# SCH_PIEZO_CRYSTAL_DAC_2022-01-11.net
KiCad netlist of a schematic drawn in EasyEDA
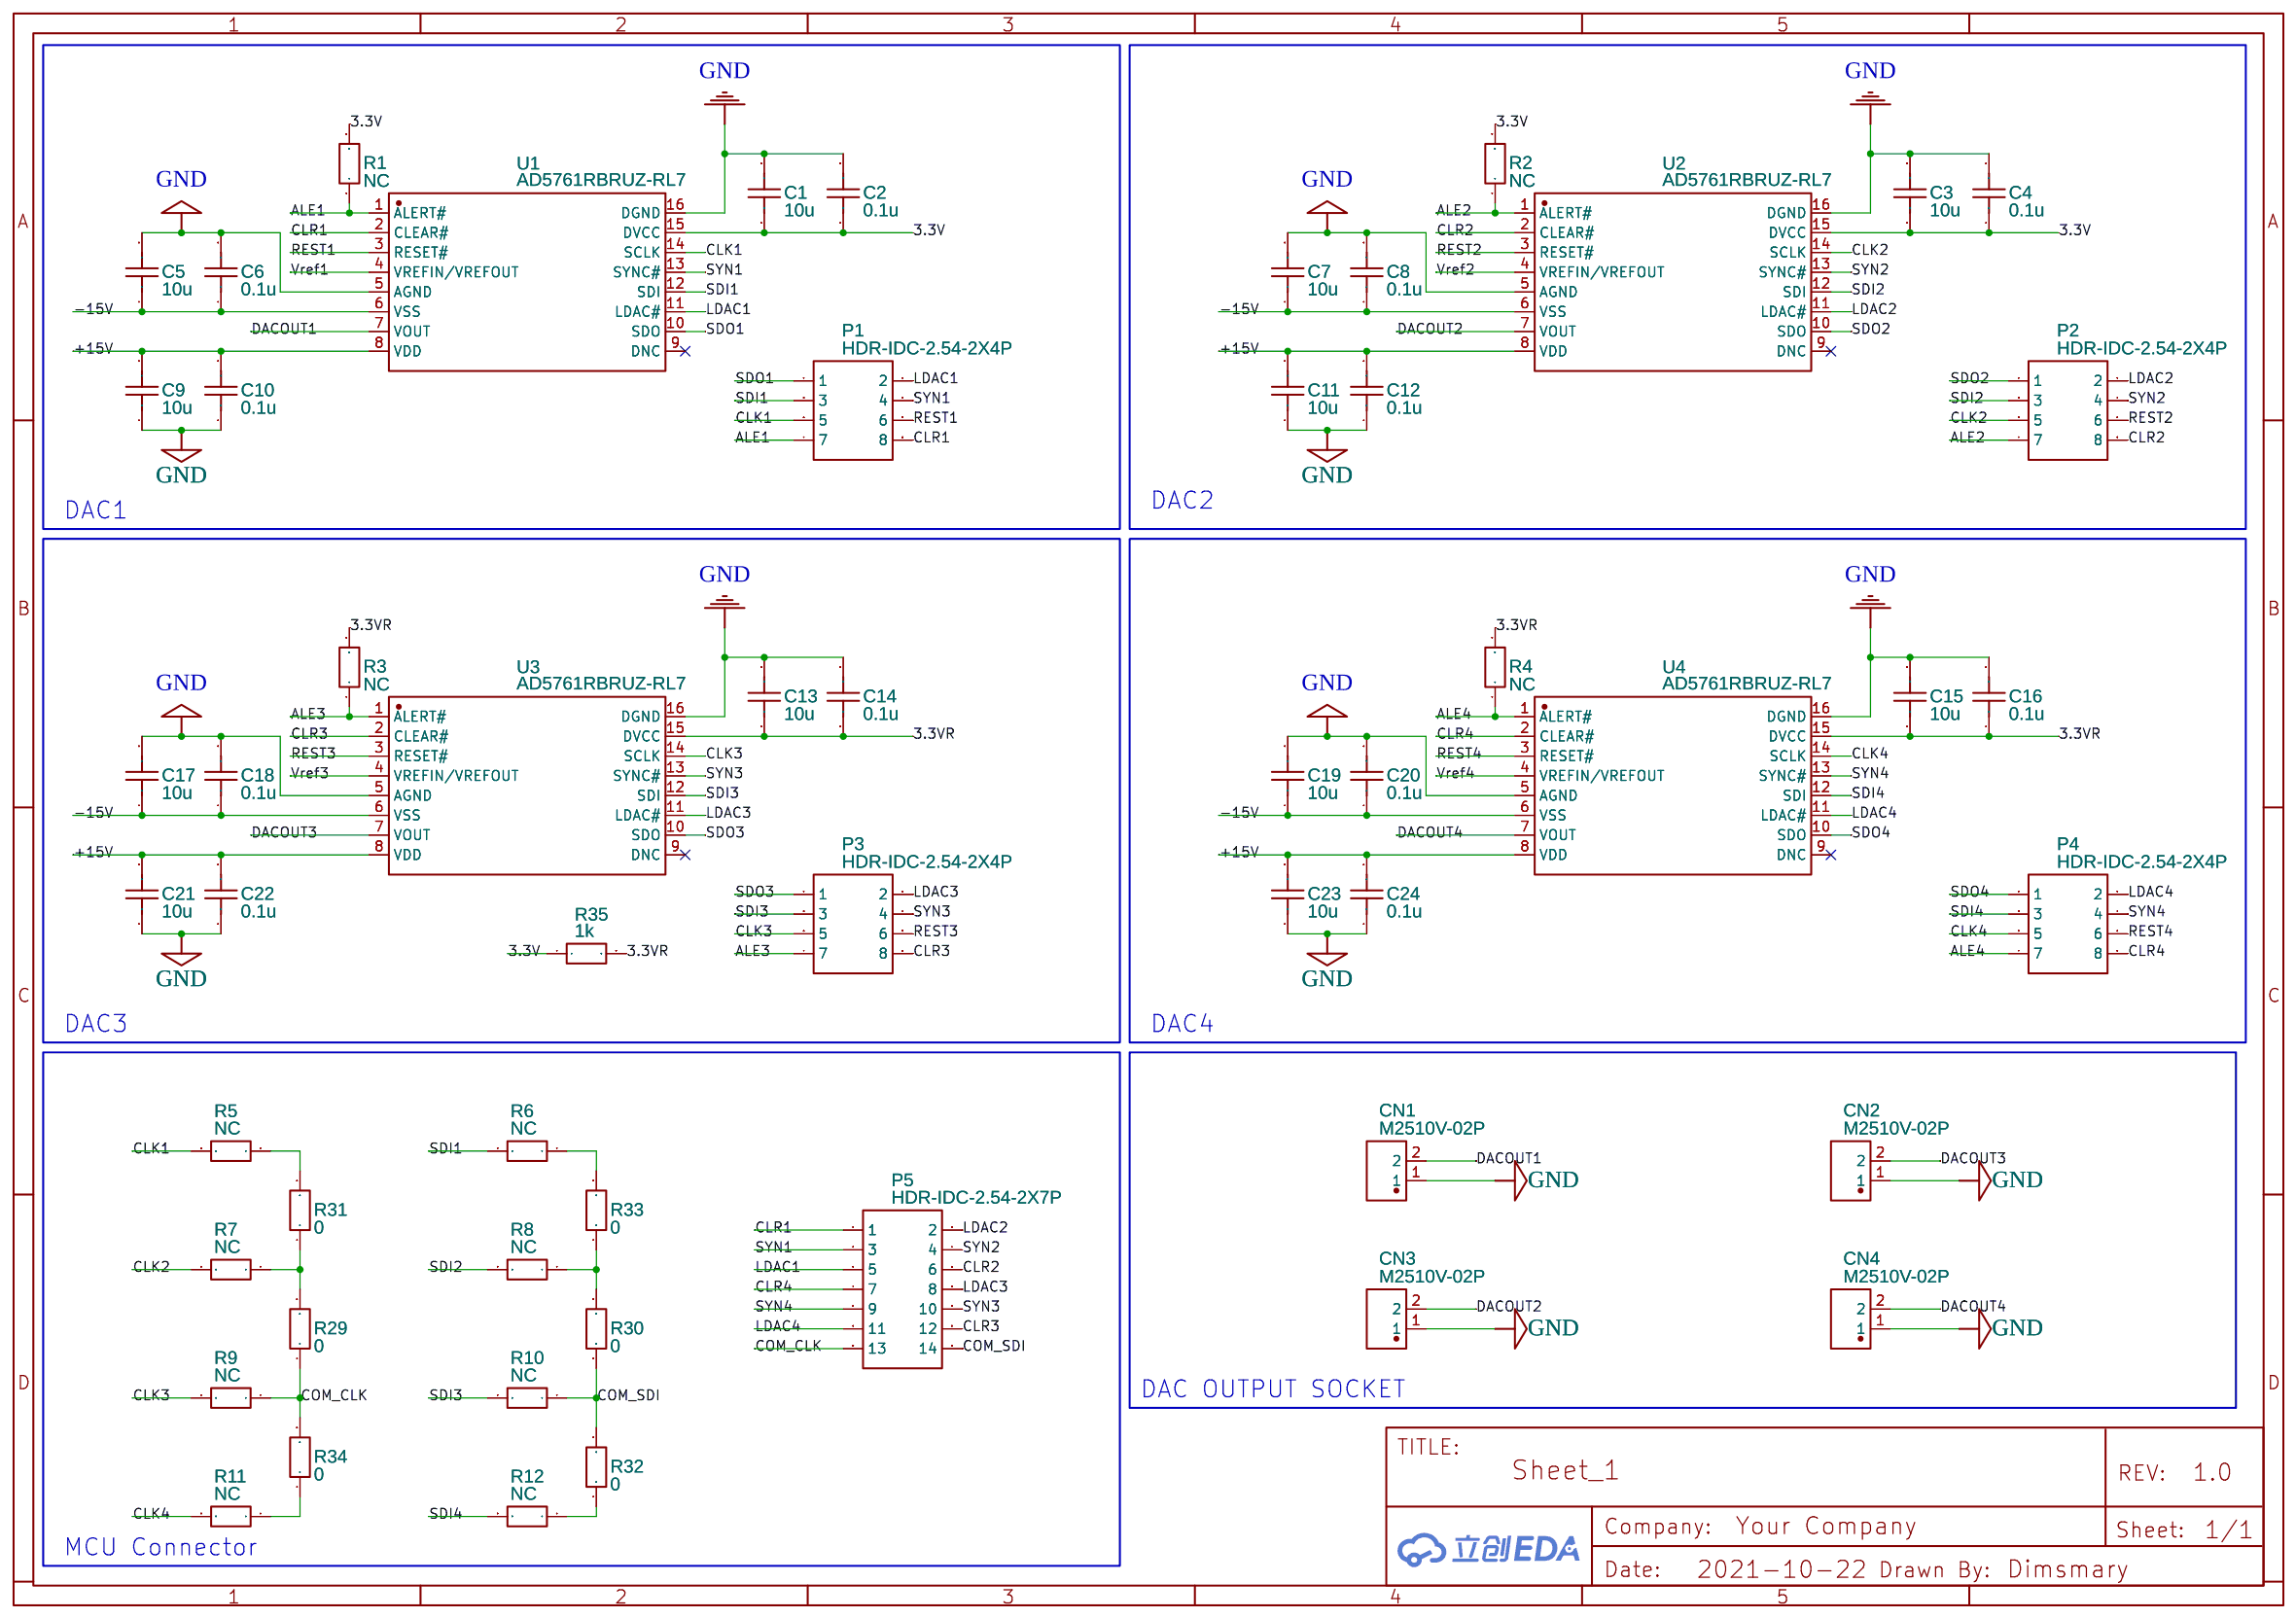
[diagram p0: DACs]
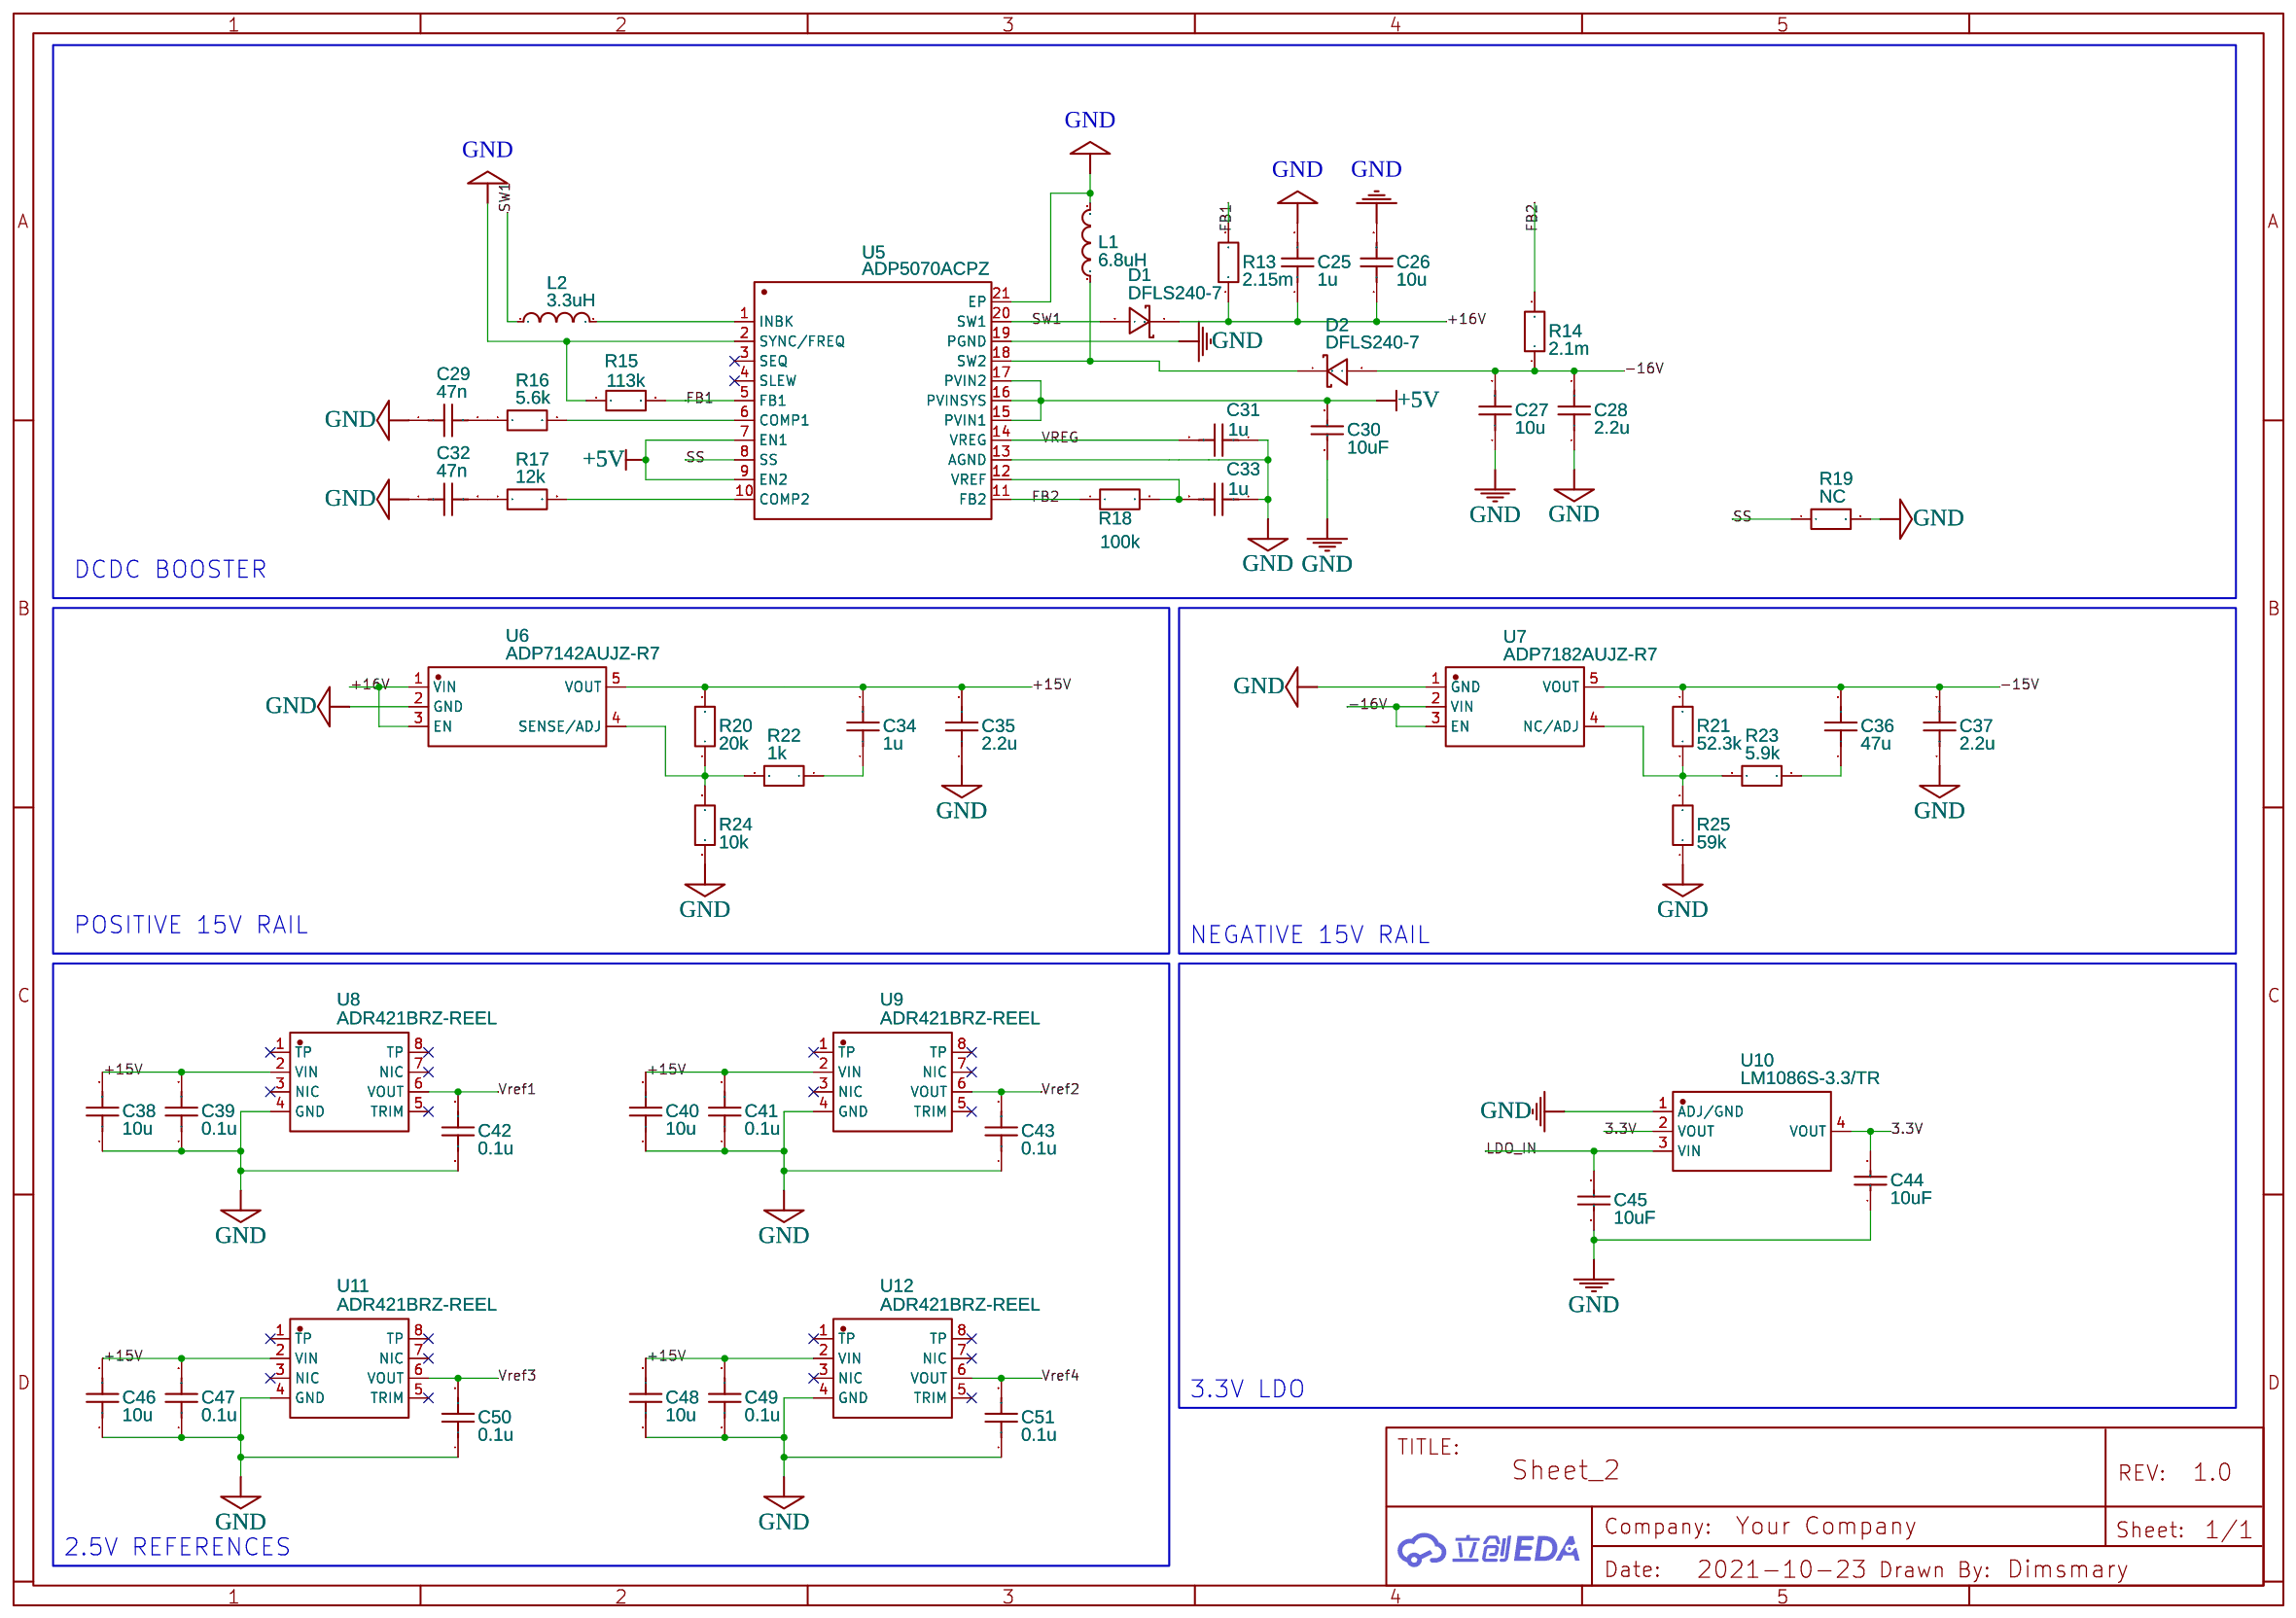
[diagram p1: PowerRail]
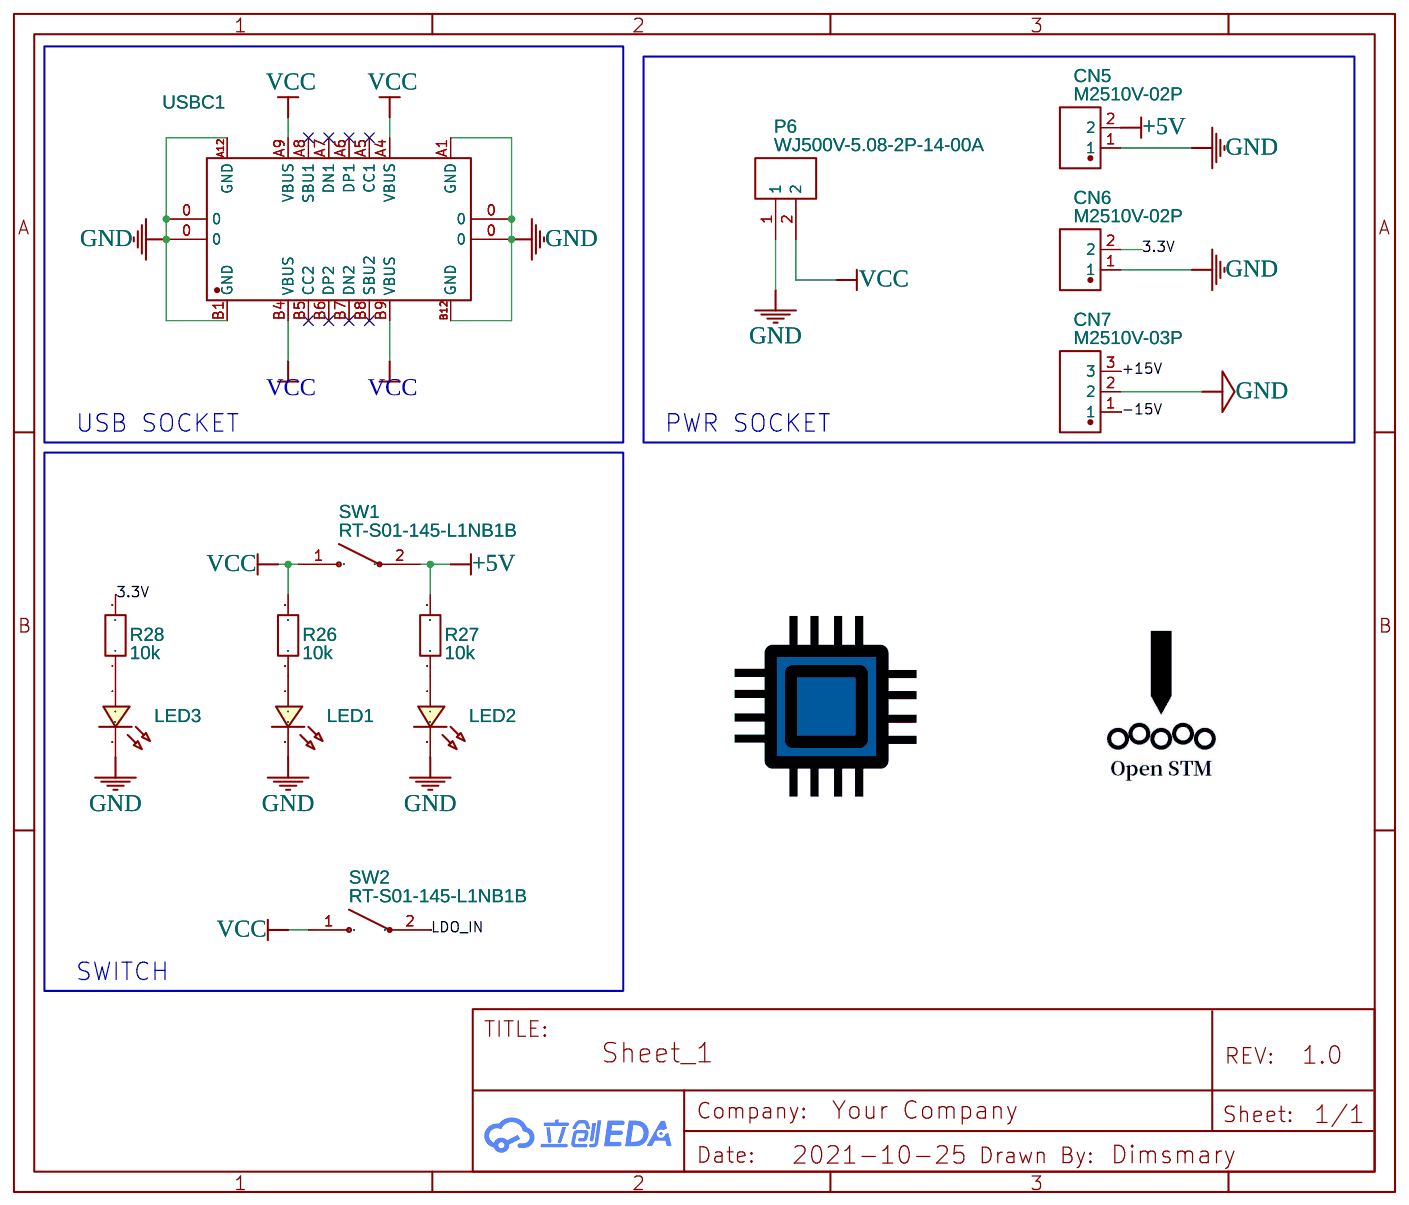
[diagram p2: PowerInput]

(export (version "E")
  (design (tool "Eeschema 10.0.6"))
  (components
    (comp (ref "C1") (value "10u") (libsource (lib "") (part "C_0603_US")))
    (comp (ref "C2") (value "0.1u") (libsource (lib "") (part "C_0603_US")))
    (comp (ref "C3") (value "10u") (libsource (lib "") (part "C_0603_US")))
    (comp (ref "C4") (value "0.1u") (libsource (lib "") (part "C_0603_US")))
    (comp (ref "C5") (value "10u") (libsource (lib "") (part "C_0603_US")))
    (comp (ref "C6") (value "0.1u") (libsource (lib "") (part "C_0603_US")))
    (comp (ref "C7") (value "10u") (libsource (lib "") (part "C_0603_US")))
    (comp (ref "C8") (value "0.1u") (libsource (lib "") (part "C_0603_US")))
    (comp (ref "C9") (value "10u") (libsource (lib "") (part "C_0603_US")))
    (comp (ref "C10") (value "0.1u") (libsource (lib "") (part "C_0603_US")))
    (comp (ref "C11") (value "10u") (libsource (lib "") (part "C_0603_US")))
    (comp (ref "C12") (value "0.1u") (libsource (lib "") (part "C_0603_US")))
    (comp (ref "C13") (value "10u") (libsource (lib "") (part "C_0603_US")))
    (comp (ref "C14") (value "0.1u") (libsource (lib "") (part "C_0603_US")))
    (comp (ref "C15") (value "10u") (libsource (lib "") (part "C_0603_US")))
    (comp (ref "C16") (value "0.1u") (libsource (lib "") (part "C_0603_US")))
    (comp (ref "C17") (value "10u") (libsource (lib "") (part "C_0603_US")))
    (comp (ref "C18") (value "0.1u") (libsource (lib "") (part "C_0603_US")))
    (comp (ref "C19") (value "10u") (libsource (lib "") (part "C_0603_US")))
    (comp (ref "C20") (value "0.1u") (libsource (lib "") (part "C_0603_US")))
    (comp (ref "C21") (value "10u") (libsource (lib "") (part "C_0603_US")))
    (comp (ref "C22") (value "0.1u") (libsource (lib "") (part "C_0603_US")))
    (comp (ref "C23") (value "10u") (libsource (lib "") (part "C_0603_US")))
    (comp (ref "C24") (value "0.1u") (libsource (lib "") (part "C_0603_US")))
    (comp (ref "CN1")
      (value "M2510V-02P")
      (fields (field (name "BOM_Supplier Part") "C2764790"))
      (libsource (lib "") (part "M2510V-02P"))
    )
    (comp (ref "CN2")
      (value "M2510V-02P")
      (fields (field (name "BOM_Supplier Part") "C2764790"))
      (libsource (lib "") (part "M2510V-02P"))
    )
    (comp (ref "CN3")
      (value "M2510V-02P")
      (fields (field (name "BOM_Supplier Part") "C2764790"))
      (libsource (lib "") (part "M2510V-02P"))
    )
    (comp (ref "CN4")
      (value "M2510V-02P")
      (fields (field (name "BOM_Supplier Part") "C2764790"))
      (libsource (lib "") (part "M2510V-02P"))
    )
    (comp (ref "P1")
      (value "HDR-IDC-2.54-2X4P")
      (fields
        (field (name "BOM_Manufacturer Part") "IDC Box 2X4 2.54MM")
        (field (name "BOM_Supplier Part") "C9135")
      )
      (libsource (lib "") (part "HDR-IDC-2.54-2X4P"))
    )
    (comp (ref "P2")
      (value "HDR-IDC-2.54-2X4P")
      (fields
        (field (name "BOM_Manufacturer Part") "IDC Box 2X4 2.54MM")
        (field (name "BOM_Supplier Part") "C9135")
      )
      (libsource (lib "") (part "HDR-IDC-2.54-2X4P"))
    )
    (comp (ref "P3")
      (value "HDR-IDC-2.54-2X4P")
      (fields
        (field (name "BOM_Manufacturer Part") "IDC Box 2X4 2.54MM")
        (field (name "BOM_Supplier Part") "C9135")
      )
      (libsource (lib "") (part "HDR-IDC-2.54-2X4P"))
    )
    (comp (ref "P4")
      (value "HDR-IDC-2.54-2X4P")
      (fields
        (field (name "BOM_Manufacturer Part") "IDC Box 2X4 2.54MM")
        (field (name "BOM_Supplier Part") "C9135")
      )
      (libsource (lib "") (part "HDR-IDC-2.54-2X4P"))
    )
    (comp (ref "P5")
      (value "HDR-IDC-2.54-2X7P")
      (fields
        (field (name "BOM_Manufacturer Part") "2X7 2.54mm IDC Box")
        (field (name "BOM_Supplier Part") "C11215")
      )
      (libsource (lib "") (part "HDR-IDC-2.54-2X7P"))
    )
    (comp (ref "R1") (value "NC") (libsource (lib "") (part "R_0603_EU_1")))
    (comp (ref "R2") (value "NC") (libsource (lib "") (part "R_0603_EU_1")))
    (comp (ref "R3") (value "NC") (libsource (lib "") (part "R_0603_EU_1")))
    (comp (ref "R4") (value "NC") (libsource (lib "") (part "R_0603_EU_1")))
    (comp (ref "R5") (value "NC") (libsource (lib "") (part "R_0603_EU")))
    (comp (ref "R6") (value "NC") (libsource (lib "") (part "R_0603_EU")))
    (comp (ref "R7") (value "NC") (libsource (lib "") (part "R_0603_EU")))
    (comp (ref "R8") (value "NC") (libsource (lib "") (part "R_0603_EU")))
    (comp (ref "R9") (value "NC") (libsource (lib "") (part "R_0603_EU")))
    (comp (ref "R10") (value "NC") (libsource (lib "") (part "R_0603_EU")))
    (comp (ref "R11") (value "NC") (libsource (lib "") (part "R_0603_EU")))
    (comp (ref "R12") (value "NC") (libsource (lib "") (part "R_0603_EU")))
    (comp (ref "R29") (value "0") (libsource (lib "") (part "R_1206_EU")))
    (comp (ref "R30") (value "0") (libsource (lib "") (part "R_1206_EU")))
    (comp (ref "R31") (value "0") (libsource (lib "") (part "R_1206_EU")))
    (comp (ref "R32") (value "0") (libsource (lib "") (part "R_1206_EU")))
    (comp (ref "R33") (value "0") (libsource (lib "") (part "R_1206_EU")))
    (comp (ref "R34") (value "0") (libsource (lib "") (part "R_1206_EU")))
    (comp (ref "R35") (value "1k") (libsource (lib "") (part "R_2512_EU")))
    (comp (ref "U1")
      (value "AD5761RBRUZ-RL7")
      (fields (field (name "BOM_Supplier Part") "C515877"))
      (libsource (lib "") (part "AD5761RBRUZ-RL7"))
    )
    (comp (ref "U2")
      (value "AD5761RBRUZ-RL7")
      (fields (field (name "BOM_Supplier Part") "C515877"))
      (libsource (lib "") (part "AD5761RBRUZ-RL7"))
    )
    (comp (ref "U3")
      (value "AD5761RBRUZ-RL7")
      (fields (field (name "BOM_Supplier Part") "C515877"))
      (libsource (lib "") (part "AD5761RBRUZ-RL7"))
    )
    (comp (ref "U4")
      (value "AD5761RBRUZ-RL7")
      (fields (field (name "BOM_Supplier Part") "C515877"))
      (libsource (lib "") (part "AD5761RBRUZ-RL7"))
    )
    (comp (ref "C25") (value "1u") (libsource (lib "") (part "C_0603_US")))
    (comp (ref "C26") (value "10u") (libsource (lib "") (part "C_0603_US")))
    (comp (ref "C27") (value "10u") (libsource (lib "") (part "C_0603_US")))
    (comp (ref "C28") (value "2.2u") (libsource (lib "") (part "C_0603_US")))
    (comp (ref "C29") (value "47n") (libsource (lib "") (part "C_0603_US_2")))
    (comp (ref "C30")
      (value "10uF")
      (fields
        (field (name "BOM_Manufacturer Part") "CL21A106KOQNNNE")
        (field (name "BOM_Supplier Part") "C1713")
      )
      (libsource (lib "") (part "CL21A106KOQNNNE"))
    )
    (comp (ref "C31") (value "1u") (libsource (lib "") (part "C_0603_US_1")))
    (comp (ref "C32") (value "47n") (libsource (lib "") (part "C_0603_US_2")))
    (comp (ref "C33") (value "1u") (libsource (lib "") (part "C_0603_US_1")))
    (comp (ref "C34") (value "1u") (libsource (lib "") (part "C_0603_US")))
    (comp (ref "C35") (value "2.2u") (libsource (lib "") (part "C_0603_US")))
    (comp (ref "C36") (value "47u") (libsource (lib "") (part "C_0603_US")))
    (comp (ref "C37") (value "2.2u") (libsource (lib "") (part "C_0603_US")))
    (comp (ref "C38") (value "10u") (libsource (lib "") (part "C_0603_US")))
    (comp (ref "C39") (value "0.1u") (libsource (lib "") (part "C_0603_US")))
    (comp (ref "C40") (value "10u") (libsource (lib "") (part "C_0603_US")))
    (comp (ref "C41") (value "0.1u") (libsource (lib "") (part "C_0603_US")))
    (comp (ref "C42") (value "0.1u") (libsource (lib "") (part "C_0603_US")))
    (comp (ref "C43") (value "0.1u") (libsource (lib "") (part "C_0603_US")))
    (comp (ref "C44")
      (value "10uF")
      (fields
        (field (name "BOM_Manufacturer Part") "CL21A106KOQNNNE")
        (field (name "BOM_Supplier Part") "C1713")
      )
      (libsource (lib "") (part "CL21A106KOQNNNE"))
    )
    (comp (ref "C45")
      (value "10uF")
      (fields
        (field (name "BOM_Manufacturer Part") "CL21A106KOQNNNE")
        (field (name "BOM_Supplier Part") "C1713")
      )
      (libsource (lib "") (part "CL21A106KOQNNNE"))
    )
    (comp (ref "C46") (value "10u") (libsource (lib "") (part "C_0603_US")))
    (comp (ref "C47") (value "0.1u") (libsource (lib "") (part "C_0603_US")))
    (comp (ref "C48") (value "10u") (libsource (lib "") (part "C_0603_US")))
    (comp (ref "C49") (value "0.1u") (libsource (lib "") (part "C_0603_US")))
    (comp (ref "C50") (value "0.1u") (libsource (lib "") (part "C_0603_US")))
    (comp (ref "C51") (value "0.1u") (libsource (lib "") (part "C_0603_US")))
    (comp (ref "D1")
      (value "DFLS240-7")
      (fields (field (name "BOM_Supplier Part") "C124195"))
      (libsource (lib "") (part "DFLS240-7"))
    )
    (comp (ref "D2")
      (value "DFLS240-7")
      (fields (field (name "BOM_Supplier Part") "C124195"))
      (libsource (lib "") (part "DFLS240-7_1"))
    )
    (comp (ref "L1")
      (value "6.8uH")
      (fields
        (field (name "BOM_Manufacturer Part") "LBM2016T6R8J")
        (field (name "BOM_Supplier Part") "C222609")
      )
      (libsource (lib "") (part "LBM2016T6R8J"))
    )
    (comp (ref "L2")
      (value "3.3uH")
      (fields
        (field (name "BOM_Manufacturer Part") "LBM2016T3R3J")
        (field (name "BOM_Supplier Part") "C222605")
      )
      (libsource (lib "") (part "LBM2016T3R3J"))
    )
    (comp (ref "R13") (value "2.15m") (libsource (lib "") (part "R_0603_EU")))
    (comp (ref "R14") (value "2.1m") (libsource (lib "") (part "R_0603_EU")))
    (comp (ref "R15") (value "113k") (libsource (lib "") (part "R_0603_EU_2")))
    (comp (ref "R16") (value "5.6k") (libsource (lib "") (part "R_0603_EU_2")))
    (comp (ref "R17") (value "12k") (libsource (lib "") (part "R_0603_EU_2")))
    (comp (ref "R18") (value "100k") (libsource (lib "") (part "R_0603_EU_2")))
    (comp (ref "R19") (value "NC") (libsource (lib "") (part "R_0603_EU_2")))
    (comp (ref "R20") (value "20k") (libsource (lib "") (part "R_0603_EU")))
    (comp (ref "R21") (value "52.3k") (libsource (lib "") (part "R_0603_EU")))
    (comp (ref "R22") (value "1k") (libsource (lib "") (part "R_0603_EU_1")))
    (comp (ref "R23") (value "5.9k") (libsource (lib "") (part "R_0603_EU_1")))
    (comp (ref "R24") (value "10k") (libsource (lib "") (part "R_0603_EU")))
    (comp (ref "R25") (value "59k") (libsource (lib "") (part "R_0603_EU")))
    (comp (ref "U5")
      (value "ADP5070ACPZ")
      (fields (field (name "BOM_Supplier Part") "C659267"))
      (libsource (lib "") (part "ADP5070ACPZ"))
    )
    (comp (ref "U6")
      (value "ADP7142AUJZ-R7")
      (fields (field (name "BOM_Supplier Part") "C514356"))
      (libsource (lib "") (part "ADP7142AUJZ-R7"))
    )
    (comp (ref "U7")
      (value "ADP7182AUJZ-R7")
      (fields (field (name "BOM_Supplier Part") "C514358"))
      (libsource (lib "") (part "ADP7182AUJZ-R7"))
    )
    (comp (ref "U8")
      (value "ADR421BRZ-REEL")
      (fields (field (name "BOM_Supplier Part") "C496503"))
      (libsource (lib "") (part "ADR421BRZ-REEL"))
    )
    (comp (ref "U9")
      (value "ADR421BRZ-REEL")
      (fields (field (name "BOM_Supplier Part") "C496503"))
      (libsource (lib "") (part "ADR421BRZ-REEL"))
    )
    (comp (ref "U10")
      (value "LM1086S-3.3/TR")
      (fields (field (name "BOM_Supplier Part") "C444378"))
      (libsource (lib "") (part "LM1086S-3.3/TR"))
    )
    (comp (ref "U11")
      (value "ADR421BRZ-REEL")
      (fields (field (name "BOM_Supplier Part") "C496503"))
      (libsource (lib "") (part "ADR421BRZ-REEL"))
    )
    (comp (ref "U12")
      (value "ADR421BRZ-REEL")
      (fields (field (name "BOM_Supplier Part") "C496503"))
      (libsource (lib "") (part "ADR421BRZ-REEL"))
    )
    (comp (ref "CN5")
      (value "M2510V-02P")
      (fields (field (name "BOM_Supplier Part") "C2764790"))
      (libsource (lib "") (part "M2510V-02P"))
    )
    (comp (ref "CN6")
      (value "M2510V-02P")
      (fields (field (name "BOM_Supplier Part") "C2764790"))
      (libsource (lib "") (part "M2510V-02P"))
    )
    (comp (ref "CN7")
      (value "M2510V-03P")
      (fields (field (name "BOM_Supplier Part") "C2764791"))
      (libsource (lib "") (part "M2510V-03P"))
    )
    (comp (ref "LED1")
      (value "LED-0603_R")
      (fields
        (field (name "BOM_Manufacturer Part") "19-217/R6C-AL1M2VY/3T")
        (field (name "BOM_Supplier Part") "C72044")
      )
      (libsource (lib "") (part "LED-0603_R"))
    )
    (comp (ref "LED2")
      (value "LED-0603_R")
      (fields
        (field (name "BOM_Manufacturer Part") "19-217/R6C-AL1M2VY/3T")
        (field (name "BOM_Supplier Part") "C72044")
      )
      (libsource (lib "") (part "LED-0603_R"))
    )
    (comp (ref "LED3")
      (value "LED-0603_R")
      (fields
        (field (name "BOM_Manufacturer Part") "19-217/R6C-AL1M2VY/3T")
        (field (name "BOM_Supplier Part") "C72044")
      )
      (libsource (lib "") (part "LED-0603_R"))
    )
    (comp (ref "P6")
      (value "WJ500V-5.08-2P-14-00A")
      (fields (field (name "BOM_Supplier Part") "C8465"))
      (libsource (lib "") (part "WJ500V-5.08-2P-14-00A"))
    )
    (comp (ref "R26") (value "10k") (libsource (lib "") (part "R_0603_EU")))
    (comp (ref "R27") (value "10k") (libsource (lib "") (part "R_0603_EU")))
    (comp (ref "R28") (value "10k") (libsource (lib "") (part "R_0603_EU")))
    (comp (ref "SW1")
      (value "RT-S01-145-L1NB1B")
      (fields (field (name "BOM_Supplier Part") "C312627"))
      (libsource (lib "") (part "RT-S01-145-L1NB1B"))
    )
    (comp (ref "SW2")
      (value "RT-S01-145-L1NB1B")
      (fields (field (name "BOM_Supplier Part") "C312627"))
      (libsource (lib "") (part "RT-S01-145-L1NB1B"))
    )
    (comp (ref "USBC1")
      (value "TYPE-C-31-M-12")
      (fields (field (name "BOM_Supplier Part") "C165948"))
      (libsource (lib "") (part "Unknown_165_-705"))
    )
  )
  (nets
    (net (code "1") (name "+5V") (class "Default")
      (node (ref "C30") (pin "2") (pinfunction "2_2") (pintype "input"))
      (node (ref "CN5") (pin "2") (pinfunction "2_2") (pintype "unspecified"))
      (node (ref "R27") (pin "2") (pinfunction "2_2") (pintype "unspecified"))
      (node (ref "SW1") (pin "2") (pinfunction "2_2") (pintype "unspecified"))
      (node (ref "U5") (pin "15") (pinfunction "PVIN1_15") (pintype "unspecified"))
      (node (ref "U5") (pin "16") (pinfunction "PVINSYS_16") (pintype "unspecified"))
      (node (ref "U5") (pin "17") (pinfunction "PVIN2_17") (pintype "unspecified"))
      (node (ref "U5") (pin "7") (pinfunction "EN1_7") (pintype "unspecified"))
      (node (ref "U5") (pin "9") (pinfunction "EN2_9") (pintype "unspecified"))
    )
    (net (code "2") (name "+15V") (class "Default")
      (node (ref "C10") (pin "2") (pinfunction "2_2") (pintype "unspecified"))
      (node (ref "C11") (pin "2") (pinfunction "2_2") (pintype "unspecified"))
      (node (ref "C12") (pin "2") (pinfunction "2_2") (pintype "unspecified"))
      (node (ref "C21") (pin "2") (pinfunction "2_2") (pintype "unspecified"))
      (node (ref "C22") (pin "2") (pinfunction "2_2") (pintype "unspecified"))
      (node (ref "C23") (pin "2") (pinfunction "2_2") (pintype "unspecified"))
      (node (ref "C24") (pin "2") (pinfunction "2_2") (pintype "unspecified"))
      (node (ref "C34") (pin "2") (pinfunction "2_2") (pintype "unspecified"))
      (node (ref "C35") (pin "2") (pinfunction "2_2") (pintype "unspecified"))
      (node (ref "C38") (pin "2") (pinfunction "2_2") (pintype "unspecified"))
      (node (ref "C39") (pin "2") (pinfunction "2_2") (pintype "unspecified"))
      (node (ref "C40") (pin "2") (pinfunction "2_2") (pintype "unspecified"))
      (node (ref "C41") (pin "2") (pinfunction "2_2") (pintype "unspecified"))
      (node (ref "C46") (pin "2") (pinfunction "2_2") (pintype "unspecified"))
      (node (ref "C47") (pin "2") (pinfunction "2_2") (pintype "unspecified"))
      (node (ref "C48") (pin "2") (pinfunction "2_2") (pintype "unspecified"))
      (node (ref "C49") (pin "2") (pinfunction "2_2") (pintype "unspecified"))
      (node (ref "C9") (pin "2") (pinfunction "2_2") (pintype "unspecified"))
      (node (ref "CN7") (pin "3") (pinfunction "3_3") (pintype "unspecified"))
      (node (ref "R20") (pin "2") (pinfunction "2_2") (pintype "unspecified"))
      (node (ref "U1") (pin "8") (pinfunction "VDD_8") (pintype "unspecified"))
      (node (ref "U11") (pin "2") (pinfunction "VIN_2") (pintype "unspecified"))
      (node (ref "U12") (pin "2") (pinfunction "VIN_2") (pintype "unspecified"))
      (node (ref "U2") (pin "8") (pinfunction "VDD_8") (pintype "unspecified"))
      (node (ref "U3") (pin "8") (pinfunction "VDD_8") (pintype "unspecified"))
      (node (ref "U4") (pin "8") (pinfunction "VDD_8") (pintype "unspecified"))
      (node (ref "U6") (pin "5") (pinfunction "VOUT_5") (pintype "unspecified"))
      (node (ref "U8") (pin "2") (pinfunction "VIN_2") (pintype "unspecified"))
      (node (ref "U9") (pin "2") (pinfunction "VIN_2") (pintype "unspecified"))
    )
    (net (code "3") (name "+16V") (class "Default")
      (node (ref "C25") (pin "1") (pinfunction "1_1") (pintype "unspecified"))
      (node (ref "C26") (pin "1") (pinfunction "1_1") (pintype "unspecified"))
      (node (ref "D1") (pin "1") (pinfunction "C_1") (pintype "unspecified"))
      (node (ref "R13") (pin "1") (pinfunction "1_1") (pintype "unspecified"))
      (node (ref "U6") (pin "1") (pinfunction "VIN_1") (pintype "unspecified"))
      (node (ref "U6") (pin "3") (pinfunction "EN_3") (pintype "unspecified"))
    )
    (net (code "4") (name "-15V") (class "Default")
      (node (ref "C17") (pin "1") (pinfunction "1_1") (pintype "unspecified"))
      (node (ref "C18") (pin "1") (pinfunction "1_1") (pintype "unspecified"))
      (node (ref "C19") (pin "1") (pinfunction "1_1") (pintype "unspecified"))
      (node (ref "C20") (pin "1") (pinfunction "1_1") (pintype "unspecified"))
      (node (ref "C36") (pin "2") (pinfunction "2_2") (pintype "unspecified"))
      (node (ref "C37") (pin "2") (pinfunction "2_2") (pintype "unspecified"))
      (node (ref "C5") (pin "1") (pinfunction "1_1") (pintype "unspecified"))
      (node (ref "C6") (pin "1") (pinfunction "1_1") (pintype "unspecified"))
      (node (ref "C7") (pin "1") (pinfunction "1_1") (pintype "unspecified"))
      (node (ref "C8") (pin "1") (pinfunction "1_1") (pintype "unspecified"))
      (node (ref "CN7") (pin "1") (pinfunction "1_1") (pintype "unspecified"))
      (node (ref "R21") (pin "2") (pinfunction "2_2") (pintype "unspecified"))
      (node (ref "U1") (pin "6") (pinfunction "VSS_6") (pintype "unspecified"))
      (node (ref "U2") (pin "6") (pinfunction "VSS_6") (pintype "unspecified"))
      (node (ref "U3") (pin "6") (pinfunction "VSS_6") (pintype "unspecified"))
      (node (ref "U4") (pin "6") (pinfunction "VSS_6") (pintype "unspecified"))
      (node (ref "U7") (pin "5") (pinfunction "VOUT_5") (pintype "unspecified"))
    )
    (net (code "5") (name "-16V") (class "Default")
      (node (ref "C27") (pin "2") (pinfunction "2_2") (pintype "unspecified"))
      (node (ref "C28") (pin "2") (pinfunction "2_2") (pintype "unspecified"))
      (node (ref "D2") (pin "2") (pinfunction "A_2") (pintype "unspecified"))
      (node (ref "R14") (pin "1") (pinfunction "1_1") (pintype "unspecified"))
      (node (ref "U7") (pin "2") (pinfunction "VIN_2") (pintype "unspecified"))
      (node (ref "U7") (pin "3") (pinfunction "EN_3") (pintype "unspecified"))
    )
    (net (code "6") (name "3.3V") (class "Default")
      (node (ref "C1") (pin "1") (pinfunction "1_1") (pintype "unspecified"))
      (node (ref "C2") (pin "1") (pinfunction "1_1") (pintype "unspecified"))
      (node (ref "C3") (pin "1") (pinfunction "1_1") (pintype "unspecified"))
      (node (ref "C4") (pin "1") (pinfunction "1_1") (pintype "unspecified"))
      (node (ref "C44") (pin "2") (pinfunction "2_2") (pintype "input"))
      (node (ref "CN6") (pin "2") (pinfunction "2_2") (pintype "unspecified"))
      (node (ref "R1") (pin "2") (pinfunction "2_2") (pintype "unspecified"))
      (node (ref "R2") (pin "2") (pinfunction "2_2") (pintype "unspecified"))
      (node (ref "R28") (pin "2") (pinfunction "2_2") (pintype "unspecified"))
      (node (ref "R35") (pin "1") (pinfunction "1_1") (pintype "unspecified"))
      (node (ref "U1") (pin "15") (pinfunction "DVCC_15") (pintype "unspecified"))
      (node (ref "U10") (pin "2") (pinfunction "VOUT_2") (pintype "unspecified"))
      (node (ref "U10") (pin "4") (pinfunction "VOUT_4") (pintype "unspecified"))
      (node (ref "U2") (pin "15") (pinfunction "DVCC_15") (pintype "unspecified"))
    )
    (net (code "7") (name "3.3VR") (class "Default")
      (node (ref "C13") (pin "1") (pinfunction "1_1") (pintype "unspecified"))
      (node (ref "C14") (pin "1") (pinfunction "1_1") (pintype "unspecified"))
      (node (ref "C15") (pin "1") (pinfunction "1_1") (pintype "unspecified"))
      (node (ref "C16") (pin "1") (pinfunction "1_1") (pintype "unspecified"))
      (node (ref "R3") (pin "2") (pinfunction "2_2") (pintype "unspecified"))
      (node (ref "R35") (pin "2") (pinfunction "2_2") (pintype "unspecified"))
      (node (ref "R4") (pin "2") (pinfunction "2_2") (pintype "unspecified"))
      (node (ref "U3") (pin "15") (pinfunction "DVCC_15") (pintype "unspecified"))
      (node (ref "U4") (pin "15") (pinfunction "DVCC_15") (pintype "unspecified"))
    )
    (net (code "8") (name "ALE1") (class "Default")
      (node (ref "P1") (pin "7") (pinfunction "7_7") (pintype "unspecified"))
      (node (ref "R1") (pin "1") (pinfunction "1_1") (pintype "unspecified"))
      (node (ref "U1") (pin "1") (pinfunction "ALERT#_1") (pintype "unspecified"))
    )
    (net (code "9") (name "ALE2") (class "Default")
      (node (ref "P2") (pin "7") (pinfunction "7_7") (pintype "unspecified"))
      (node (ref "R2") (pin "1") (pinfunction "1_1") (pintype "unspecified"))
      (node (ref "U2") (pin "1") (pinfunction "ALERT#_1") (pintype "unspecified"))
    )
    (net (code "10") (name "ALE3") (class "Default")
      (node (ref "P3") (pin "7") (pinfunction "7_7") (pintype "unspecified"))
      (node (ref "R3") (pin "1") (pinfunction "1_1") (pintype "unspecified"))
      (node (ref "U3") (pin "1") (pinfunction "ALERT#_1") (pintype "unspecified"))
    )
    (net (code "11") (name "ALE4") (class "Default")
      (node (ref "P4") (pin "7") (pinfunction "7_7") (pintype "unspecified"))
      (node (ref "R4") (pin "1") (pinfunction "1_1") (pintype "unspecified"))
      (node (ref "U4") (pin "1") (pinfunction "ALERT#_1") (pintype "unspecified"))
    )
    (net (code "12") (name "CLK1") (class "Default")
      (node (ref "P1") (pin "5") (pinfunction "5_5") (pintype "unspecified"))
      (node (ref "R5") (pin "2") (pinfunction "2_2") (pintype "unspecified"))
      (node (ref "U1") (pin "14") (pinfunction "SCLK_14") (pintype "unspecified"))
    )
    (net (code "13") (name "CLK2") (class "Default")
      (node (ref "P2") (pin "5") (pinfunction "5_5") (pintype "unspecified"))
      (node (ref "R7") (pin "2") (pinfunction "2_2") (pintype "unspecified"))
      (node (ref "U2") (pin "14") (pinfunction "SCLK_14") (pintype "unspecified"))
    )
    (net (code "14") (name "CLK3") (class "Default")
      (node (ref "P3") (pin "5") (pinfunction "5_5") (pintype "unspecified"))
      (node (ref "R9") (pin "2") (pinfunction "2_2") (pintype "unspecified"))
      (node (ref "U3") (pin "14") (pinfunction "SCLK_14") (pintype "unspecified"))
    )
    (net (code "15") (name "CLK4") (class "Default")
      (node (ref "P4") (pin "5") (pinfunction "5_5") (pintype "unspecified"))
      (node (ref "R11") (pin "2") (pinfunction "2_2") (pintype "unspecified"))
      (node (ref "U4") (pin "14") (pinfunction "SCLK_14") (pintype "unspecified"))
    )
    (net (code "16") (name "CLR1") (class "Default")
      (node (ref "P1") (pin "8") (pinfunction "8_8") (pintype "unspecified"))
      (node (ref "P5") (pin "1") (pinfunction "1_1") (pintype "unspecified"))
      (node (ref "U1") (pin "2") (pinfunction "CLEAR#_2") (pintype "unspecified"))
    )
    (net (code "17") (name "CLR2") (class "Default")
      (node (ref "P2") (pin "8") (pinfunction "8_8") (pintype "unspecified"))
      (node (ref "P5") (pin "6") (pinfunction "6_6") (pintype "unspecified"))
      (node (ref "U2") (pin "2") (pinfunction "CLEAR#_2") (pintype "unspecified"))
    )
    (net (code "18") (name "CLR3") (class "Default")
      (node (ref "P3") (pin "8") (pinfunction "8_8") (pintype "unspecified"))
      (node (ref "P5") (pin "12") (pinfunction "12_12") (pintype "unspecified"))
      (node (ref "U3") (pin "2") (pinfunction "CLEAR#_2") (pintype "unspecified"))
    )
    (net (code "19") (name "CLR4") (class "Default")
      (node (ref "P4") (pin "8") (pinfunction "8_8") (pintype "unspecified"))
      (node (ref "P5") (pin "7") (pinfunction "7_7") (pintype "unspecified"))
      (node (ref "U4") (pin "2") (pinfunction "CLEAR#_2") (pintype "unspecified"))
    )
    (net (code "20") (name "COM_CLK") (class "Default")
      (node (ref "P5") (pin "13") (pinfunction "13_13") (pintype "unspecified"))
      (node (ref "R29") (pin "1") (pinfunction "1_1") (pintype "unspecified"))
      (node (ref "R34") (pin "2") (pinfunction "2_2") (pintype "unspecified"))
      (node (ref "R9") (pin "1") (pinfunction "1_1") (pintype "unspecified"))
    )
    (net (code "21") (name "COM_SDI") (class "Default")
      (node (ref "P5") (pin "14") (pinfunction "14_14") (pintype "unspecified"))
      (node (ref "R10") (pin "1") (pinfunction "1_1") (pintype "unspecified"))
      (node (ref "R30") (pin "1") (pinfunction "1_1") (pintype "unspecified"))
      (node (ref "R32") (pin "2") (pinfunction "2_2") (pintype "unspecified"))
    )
    (net (code "22") (name "DACOUT1") (class "Default")
      (node (ref "CN1") (pin "2") (pinfunction "2_2") (pintype "unspecified"))
      (node (ref "U1") (pin "7") (pinfunction "VOUT_7") (pintype "unspecified"))
    )
    (net (code "23") (name "DACOUT2") (class "Default")
      (node (ref "CN3") (pin "2") (pinfunction "2_2") (pintype "unspecified"))
      (node (ref "U2") (pin "7") (pinfunction "VOUT_7") (pintype "unspecified"))
    )
    (net (code "24") (name "DACOUT3") (class "Default")
      (node (ref "CN2") (pin "2") (pinfunction "2_2") (pintype "unspecified"))
      (node (ref "U3") (pin "7") (pinfunction "VOUT_7") (pintype "unspecified"))
    )
    (net (code "25") (name "DACOUT4") (class "Default")
      (node (ref "CN4") (pin "2") (pinfunction "2_2") (pintype "unspecified"))
      (node (ref "U4") (pin "7") (pinfunction "VOUT_7") (pintype "unspecified"))
    )
    (net (code "26") (name "FB1") (class "Default")
      (node (ref "R13") (pin "2") (pinfunction "2_2") (pintype "unspecified"))
      (node (ref "R15") (pin "2") (pinfunction "2_2") (pintype "unspecified"))
      (node (ref "U5") (pin "5") (pinfunction "FB1_5") (pintype "unspecified"))
    )
    (net (code "27") (name "FB2") (class "Default")
      (node (ref "R14") (pin "2") (pinfunction "2_2") (pintype "unspecified"))
      (node (ref "R18") (pin "1") (pinfunction "1_1") (pintype "unspecified"))
      (node (ref "U5") (pin "11") (pinfunction "FB2_11") (pintype "unspecified"))
    )
    (net (code "28") (name "GND") (class "Default")
      (node (ref "C1") (pin "2") (pinfunction "2_2") (pintype "unspecified"))
      (node (ref "C10") (pin "1") (pinfunction "1_1") (pintype "unspecified"))
      (node (ref "C11") (pin "1") (pinfunction "1_1") (pintype "unspecified"))
      (node (ref "C12") (pin "1") (pinfunction "1_1") (pintype "unspecified"))
      (node (ref "C13") (pin "2") (pinfunction "2_2") (pintype "unspecified"))
      (node (ref "C14") (pin "2") (pinfunction "2_2") (pintype "unspecified"))
      (node (ref "C15") (pin "2") (pinfunction "2_2") (pintype "unspecified"))
      (node (ref "C16") (pin "2") (pinfunction "2_2") (pintype "unspecified"))
      (node (ref "C17") (pin "2") (pinfunction "2_2") (pintype "unspecified"))
      (node (ref "C18") (pin "2") (pinfunction "2_2") (pintype "unspecified"))
      (node (ref "C19") (pin "2") (pinfunction "2_2") (pintype "unspecified"))
      (node (ref "C2") (pin "2") (pinfunction "2_2") (pintype "unspecified"))
      (node (ref "C20") (pin "2") (pinfunction "2_2") (pintype "unspecified"))
      (node (ref "C21") (pin "1") (pinfunction "1_1") (pintype "unspecified"))
      (node (ref "C22") (pin "1") (pinfunction "1_1") (pintype "unspecified"))
      (node (ref "C23") (pin "1") (pinfunction "1_1") (pintype "unspecified"))
      (node (ref "C24") (pin "1") (pinfunction "1_1") (pintype "unspecified"))
      (node (ref "C25") (pin "2") (pinfunction "2_2") (pintype "unspecified"))
      (node (ref "C26") (pin "2") (pinfunction "2_2") (pintype "unspecified"))
      (node (ref "C27") (pin "1") (pinfunction "1_1") (pintype "unspecified"))
      (node (ref "C28") (pin "1") (pinfunction "1_1") (pintype "unspecified"))
      (node (ref "C29") (pin "1") (pinfunction "1_1") (pintype "unspecified"))
      (node (ref "C3") (pin "2") (pinfunction "2_2") (pintype "unspecified"))
      (node (ref "C30") (pin "1") (pinfunction "1_1") (pintype "input"))
      (node (ref "C31") (pin "1") (pinfunction "1_1") (pintype "unspecified"))
      (node (ref "C32") (pin "1") (pinfunction "1_1") (pintype "unspecified"))
      (node (ref "C33") (pin "1") (pinfunction "1_1") (pintype "unspecified"))
      (node (ref "C35") (pin "1") (pinfunction "1_1") (pintype "unspecified"))
      (node (ref "C37") (pin "1") (pinfunction "1_1") (pintype "unspecified"))
      (node (ref "C38") (pin "1") (pinfunction "1_1") (pintype "unspecified"))
      (node (ref "C39") (pin "1") (pinfunction "1_1") (pintype "unspecified"))
      (node (ref "C4") (pin "2") (pinfunction "2_2") (pintype "unspecified"))
      (node (ref "C40") (pin "1") (pinfunction "1_1") (pintype "unspecified"))
      (node (ref "C41") (pin "1") (pinfunction "1_1") (pintype "unspecified"))
      (node (ref "C42") (pin "1") (pinfunction "1_1") (pintype "unspecified"))
      (node (ref "C43") (pin "1") (pinfunction "1_1") (pintype "unspecified"))
      (node (ref "C44") (pin "1") (pinfunction "1_1") (pintype "input"))
      (node (ref "C45") (pin "1") (pinfunction "1_1") (pintype "input"))
      (node (ref "C46") (pin "1") (pinfunction "1_1") (pintype "unspecified"))
      (node (ref "C47") (pin "1") (pinfunction "1_1") (pintype "unspecified"))
      (node (ref "C48") (pin "1") (pinfunction "1_1") (pintype "unspecified"))
      (node (ref "C49") (pin "1") (pinfunction "1_1") (pintype "unspecified"))
      (node (ref "C5") (pin "2") (pinfunction "2_2") (pintype "unspecified"))
      (node (ref "C50") (pin "1") (pinfunction "1_1") (pintype "unspecified"))
      (node (ref "C51") (pin "1") (pinfunction "1_1") (pintype "unspecified"))
      (node (ref "C6") (pin "2") (pinfunction "2_2") (pintype "unspecified"))
      (node (ref "C7") (pin "2") (pinfunction "2_2") (pintype "unspecified"))
      (node (ref "C8") (pin "2") (pinfunction "2_2") (pintype "unspecified"))
      (node (ref "C9") (pin "1") (pinfunction "1_1") (pintype "unspecified"))
      (node (ref "CN1") (pin "1") (pinfunction "1_1") (pintype "unspecified"))
      (node (ref "CN2") (pin "1") (pinfunction "1_1") (pintype "unspecified"))
      (node (ref "CN3") (pin "1") (pinfunction "1_1") (pintype "unspecified"))
      (node (ref "CN4") (pin "1") (pinfunction "1_1") (pintype "unspecified"))
      (node (ref "CN5") (pin "1") (pinfunction "1_1") (pintype "unspecified"))
      (node (ref "CN6") (pin "1") (pinfunction "1_1") (pintype "unspecified"))
      (node (ref "CN7") (pin "2") (pinfunction "2_2") (pintype "unspecified"))
      (node (ref "L1") (pin "2") (pinfunction "2_2") (pintype "unspecified"))
      (node (ref "LED1") (pin "2") (pinfunction "2_2") (pintype "unspecified"))
      (node (ref "LED2") (pin "2") (pinfunction "2_2") (pintype "unspecified"))
      (node (ref "LED3") (pin "2") (pinfunction "2_2") (pintype "unspecified"))
      (node (ref "P6") (pin "1") (pinfunction "1_1") (pintype "unspecified"))
      (node (ref "R15") (pin "1") (pinfunction "1_1") (pintype "unspecified"))
      (node (ref "R19") (pin "2") (pinfunction "2_2") (pintype "unspecified"))
      (node (ref "R24") (pin "1") (pinfunction "1_1") (pintype "unspecified"))
      (node (ref "R25") (pin "1") (pinfunction "1_1") (pintype "unspecified"))
      (node (ref "U1") (pin "16") (pinfunction "DGND_16") (pintype "unspecified"))
      (node (ref "U1") (pin "5") (pinfunction "AGND_5") (pintype "unspecified"))
      (node (ref "U10") (pin "1") (pinfunction "ADJ/GND_1") (pintype "unspecified"))
      (node (ref "U11") (pin "4") (pinfunction "GND_4") (pintype "unspecified"))
      (node (ref "U12") (pin "4") (pinfunction "GND_4") (pintype "unspecified"))
      (node (ref "U2") (pin "16") (pinfunction "DGND_16") (pintype "unspecified"))
      (node (ref "U2") (pin "5") (pinfunction "AGND_5") (pintype "unspecified"))
      (node (ref "U3") (pin "16") (pinfunction "DGND_16") (pintype "unspecified"))
      (node (ref "U3") (pin "5") (pinfunction "AGND_5") (pintype "unspecified"))
      (node (ref "U4") (pin "16") (pinfunction "DGND_16") (pintype "unspecified"))
      (node (ref "U4") (pin "5") (pinfunction "AGND_5") (pintype "unspecified"))
      (node (ref "U5") (pin "13") (pinfunction "AGND_13") (pintype "unspecified"))
      (node (ref "U5") (pin "19") (pinfunction "PGND_19") (pintype "unspecified"))
      (node (ref "U5") (pin "2") (pinfunction "SYNC/FREQ_2") (pintype "unspecified"))
      (node (ref "U5") (pin "21") (pinfunction "EP_21") (pintype "unspecified"))
      (node (ref "U6") (pin "2") (pinfunction "GND_2") (pintype "unspecified"))
      (node (ref "U7") (pin "1") (pinfunction "GND_1") (pintype "unspecified"))
      (node (ref "U8") (pin "4") (pinfunction "GND_4") (pintype "unspecified"))
      (node (ref "U9") (pin "4") (pinfunction "GND_4") (pintype "unspecified"))
      (node (ref "USBC1") (pin "0") (pinfunction "0_0") (pintype "unspecified"))
      (node (ref "USBC1") (pin "A1") (pinfunction "GND_A1") (pintype "unspecified"))
      (node (ref "USBC1") (pin "A12") (pinfunction "GND_A12") (pintype "unspecified"))
      (node (ref "USBC1") (pin "B1") (pinfunction "GND_B1") (pintype "unspecified"))
      (node (ref "USBC1") (pin "B12") (pinfunction "GND_B12") (pintype "unspecified"))
    )
    (net (code "29") (name "LDAC1") (class "Default")
      (node (ref "P1") (pin "2") (pinfunction "2_2") (pintype "unspecified"))
      (node (ref "P5") (pin "5") (pinfunction "5_5") (pintype "unspecified"))
      (node (ref "U1") (pin "11") (pinfunction "LDAC#_11") (pintype "unspecified"))
    )
    (net (code "30") (name "LDAC2") (class "Default")
      (node (ref "P2") (pin "2") (pinfunction "2_2") (pintype "unspecified"))
      (node (ref "P5") (pin "2") (pinfunction "2_2") (pintype "unspecified"))
      (node (ref "U2") (pin "11") (pinfunction "LDAC#_11") (pintype "unspecified"))
    )
    (net (code "31") (name "LDAC3") (class "Default")
      (node (ref "P3") (pin "2") (pinfunction "2_2") (pintype "unspecified"))
      (node (ref "P5") (pin "8") (pinfunction "8_8") (pintype "unspecified"))
      (node (ref "U3") (pin "11") (pinfunction "LDAC#_11") (pintype "unspecified"))
    )
    (net (code "32") (name "LDAC4") (class "Default")
      (node (ref "P4") (pin "2") (pinfunction "2_2") (pintype "unspecified"))
      (node (ref "P5") (pin "11") (pinfunction "11_11") (pintype "unspecified"))
      (node (ref "U4") (pin "11") (pinfunction "LDAC#_11") (pintype "unspecified"))
    )
    (net (code "33") (name "LDO_IN") (class "Default")
      (node (ref "C45") (pin "2") (pinfunction "2_2") (pintype "input"))
      (node (ref "SW2") (pin "2") (pinfunction "2_2") (pintype "unspecified"))
      (node (ref "U10") (pin "3") (pinfunction "VIN_3") (pintype "unspecified"))
    )
    (net (code "34") (name "Net-(C29-Pad2)") (class "Default")
      (node (ref "C29") (pin "2") (pinfunction "2_2") (pintype "unspecified"))
      (node (ref "R16") (pin "1") (pinfunction "1_1") (pintype "unspecified"))
    )
    (net (code "35") (name "Net-(C32-Pad2)") (class "Default")
      (node (ref "C32") (pin "2") (pinfunction "2_2") (pintype "unspecified"))
      (node (ref "R17") (pin "1") (pinfunction "1_1") (pintype "unspecified"))
    )
    (net (code "36") (name "Net-(C34-Pad1)") (class "Default")
      (node (ref "C34") (pin "1") (pinfunction "1_1") (pintype "unspecified"))
      (node (ref "R22") (pin "1") (pinfunction "1_1") (pintype "unspecified"))
    )
    (net (code "37") (name "Net-(C36-Pad1)") (class "Default")
      (node (ref "C36") (pin "1") (pinfunction "1_1") (pintype "unspecified"))
      (node (ref "R23") (pin "1") (pinfunction "1_1") (pintype "unspecified"))
    )
    (net (code "38") (name "Net-(D2-C)") (class "Default")
      (node (ref "D2") (pin "1") (pinfunction "C_1") (pintype "unspecified"))
      (node (ref "L1") (pin "1") (pinfunction "1_1") (pintype "unspecified"))
      (node (ref "U5") (pin "18") (pinfunction "SW2_18") (pintype "unspecified"))
    )
    (net (code "39") (name "Net-(LED1-Pad1)") (class "Default")
      (node (ref "LED1") (pin "1") (pinfunction "1_1") (pintype "unspecified"))
      (node (ref "R26") (pin "1") (pinfunction "1_1") (pintype "unspecified"))
    )
    (net (code "40") (name "Net-(LED2-Pad1)") (class "Default")
      (node (ref "LED2") (pin "1") (pinfunction "1_1") (pintype "unspecified"))
      (node (ref "R27") (pin "1") (pinfunction "1_1") (pintype "unspecified"))
    )
    (net (code "41") (name "Net-(LED3-Pad1)") (class "Default")
      (node (ref "LED3") (pin "1") (pinfunction "1_1") (pintype "unspecified"))
      (node (ref "R28") (pin "1") (pinfunction "1_1") (pintype "unspecified"))
    )
    (net (code "42") (name "Net-(R11-Pad1)") (class "Default")
      (node (ref "R11") (pin "1") (pinfunction "1_1") (pintype "unspecified"))
      (node (ref "R34") (pin "1") (pinfunction "1_1") (pintype "unspecified"))
    )
    (net (code "43") (name "Net-(R12-Pad1)") (class "Default")
      (node (ref "R12") (pin "1") (pinfunction "1_1") (pintype "unspecified"))
      (node (ref "R32") (pin "1") (pinfunction "1_1") (pintype "unspecified"))
    )
    (net (code "44") (name "Net-(R29-Pad2)") (class "Default")
      (node (ref "R29") (pin "2") (pinfunction "2_2") (pintype "unspecified"))
      (node (ref "R31") (pin "1") (pinfunction "1_1") (pintype "unspecified"))
      (node (ref "R7") (pin "1") (pinfunction "1_1") (pintype "unspecified"))
    )
    (net (code "45") (name "Net-(R30-Pad2)") (class "Default")
      (node (ref "R30") (pin "2") (pinfunction "2_2") (pintype "unspecified"))
      (node (ref "R33") (pin "1") (pinfunction "1_1") (pintype "unspecified"))
      (node (ref "R8") (pin "1") (pinfunction "1_1") (pintype "unspecified"))
    )
    (net (code "46") (name "Net-(R31-Pad2)") (class "Default")
      (node (ref "R31") (pin "2") (pinfunction "2_2") (pintype "unspecified"))
      (node (ref "R5") (pin "1") (pinfunction "1_1") (pintype "unspecified"))
    )
    (net (code "47") (name "Net-(R33-Pad2)") (class "Default")
      (node (ref "R33") (pin "2") (pinfunction "2_2") (pintype "unspecified"))
      (node (ref "R6") (pin "1") (pinfunction "1_1") (pintype "unspecified"))
    )
    (net (code "48") (name "Net-(U5-COMP1)") (class "Default")
      (node (ref "R16") (pin "2") (pinfunction "2_2") (pintype "unspecified"))
      (node (ref "U5") (pin "6") (pinfunction "COMP1_6") (pintype "unspecified"))
    )
    (net (code "49") (name "Net-(U5-COMP2)") (class "Default")
      (node (ref "R17") (pin "2") (pinfunction "2_2") (pintype "unspecified"))
      (node (ref "U5") (pin "10") (pinfunction "COMP2_10") (pintype "unspecified"))
    )
    (net (code "50") (name "Net-(U5-INBK)") (class "Default")
      (node (ref "L2") (pin "2") (pinfunction "2_2") (pintype "unspecified"))
      (node (ref "U5") (pin "1") (pinfunction "INBK_1") (pintype "unspecified"))
    )
    (net (code "51") (name "Net-(U5-VREF)") (class "Default")
      (node (ref "C33") (pin "2") (pinfunction "2_2") (pintype "unspecified"))
      (node (ref "R18") (pin "2") (pinfunction "2_2") (pintype "unspecified"))
      (node (ref "U5") (pin "12") (pinfunction "VREF_12") (pintype "unspecified"))
    )
    (net (code "52") (name "Net-(U6-SENSE{slash}ADJ)") (class "Default")
      (node (ref "R20") (pin "1") (pinfunction "1_1") (pintype "unspecified"))
      (node (ref "R22") (pin "2") (pinfunction "2_2") (pintype "unspecified"))
      (node (ref "R24") (pin "2") (pinfunction "2_2") (pintype "unspecified"))
      (node (ref "U6") (pin "4") (pinfunction "SENSE/ADJ_4") (pintype "unspecified"))
    )
    (net (code "53") (name "Net-(U7-NC{slash}ADJ)") (class "Default")
      (node (ref "R21") (pin "1") (pinfunction "1_1") (pintype "unspecified"))
      (node (ref "R23") (pin "2") (pinfunction "2_2") (pintype "unspecified"))
      (node (ref "R25") (pin "2") (pinfunction "2_2") (pintype "unspecified"))
      (node (ref "U7") (pin "4") (pinfunction "NC/ADJ_4") (pintype "unspecified"))
    )
    (net (code "54") (name "REST1") (class "Default")
      (node (ref "P1") (pin "6") (pinfunction "6_6") (pintype "unspecified"))
      (node (ref "U1") (pin "3") (pinfunction "RESET#_3") (pintype "unspecified"))
    )
    (net (code "55") (name "REST2") (class "Default")
      (node (ref "P2") (pin "6") (pinfunction "6_6") (pintype "unspecified"))
      (node (ref "U2") (pin "3") (pinfunction "RESET#_3") (pintype "unspecified"))
    )
    (net (code "56") (name "REST3") (class "Default")
      (node (ref "P3") (pin "6") (pinfunction "6_6") (pintype "unspecified"))
      (node (ref "U3") (pin "3") (pinfunction "RESET#_3") (pintype "unspecified"))
    )
    (net (code "57") (name "REST4") (class "Default")
      (node (ref "P4") (pin "6") (pinfunction "6_6") (pintype "unspecified"))
      (node (ref "U4") (pin "3") (pinfunction "RESET#_3") (pintype "unspecified"))
    )
    (net (code "58") (name "SDI1") (class "Default")
      (node (ref "P1") (pin "3") (pinfunction "3_3") (pintype "unspecified"))
      (node (ref "R6") (pin "2") (pinfunction "2_2") (pintype "unspecified"))
      (node (ref "U1") (pin "12") (pinfunction "SDI_12") (pintype "unspecified"))
    )
    (net (code "59") (name "SDI2") (class "Default")
      (node (ref "P2") (pin "3") (pinfunction "3_3") (pintype "unspecified"))
      (node (ref "R8") (pin "2") (pinfunction "2_2") (pintype "unspecified"))
      (node (ref "U2") (pin "12") (pinfunction "SDI_12") (pintype "unspecified"))
    )
    (net (code "60") (name "SDI3") (class "Default")
      (node (ref "P3") (pin "3") (pinfunction "3_3") (pintype "unspecified"))
      (node (ref "R10") (pin "2") (pinfunction "2_2") (pintype "unspecified"))
      (node (ref "U3") (pin "12") (pinfunction "SDI_12") (pintype "unspecified"))
    )
    (net (code "61") (name "SDI4") (class "Default")
      (node (ref "P4") (pin "3") (pinfunction "3_3") (pintype "unspecified"))
      (node (ref "R12") (pin "2") (pinfunction "2_2") (pintype "unspecified"))
      (node (ref "U4") (pin "12") (pinfunction "SDI_12") (pintype "unspecified"))
    )
    (net (code "62") (name "SDO1") (class "Default")
      (node (ref "P1") (pin "1") (pinfunction "1_1") (pintype "unspecified"))
      (node (ref "U1") (pin "10") (pinfunction "SDO_10") (pintype "unspecified"))
    )
    (net (code "63") (name "SDO2") (class "Default")
      (node (ref "P2") (pin "1") (pinfunction "1_1") (pintype "unspecified"))
      (node (ref "U2") (pin "10") (pinfunction "SDO_10") (pintype "unspecified"))
    )
    (net (code "64") (name "SDO3") (class "Default")
      (node (ref "P3") (pin "1") (pinfunction "1_1") (pintype "unspecified"))
      (node (ref "U3") (pin "10") (pinfunction "SDO_10") (pintype "unspecified"))
    )
    (net (code "65") (name "SDO4") (class "Default")
      (node (ref "P4") (pin "1") (pinfunction "1_1") (pintype "unspecified"))
      (node (ref "U4") (pin "10") (pinfunction "SDO_10") (pintype "unspecified"))
    )
    (net (code "66") (name "SS") (class "Default")
      (node (ref "R19") (pin "1") (pinfunction "1_1") (pintype "unspecified"))
      (node (ref "U5") (pin "8") (pinfunction "SS_8") (pintype "unspecified"))
    )
    (net (code "67") (name "SW1") (class "Default")
      (node (ref "D1") (pin "2") (pinfunction "A_2") (pintype "unspecified"))
      (node (ref "L2") (pin "1") (pinfunction "1_1") (pintype "unspecified"))
      (node (ref "U5") (pin "20") (pinfunction "SW1_20") (pintype "unspecified"))
    )
    (net (code "68") (name "SYN1") (class "Default")
      (node (ref "P1") (pin "4") (pinfunction "4_4") (pintype "unspecified"))
      (node (ref "P5") (pin "3") (pinfunction "3_3") (pintype "unspecified"))
      (node (ref "U1") (pin "13") (pinfunction "SYNC#_13") (pintype "unspecified"))
    )
    (net (code "69") (name "SYN2") (class "Default")
      (node (ref "P2") (pin "4") (pinfunction "4_4") (pintype "unspecified"))
      (node (ref "P5") (pin "4") (pinfunction "4_4") (pintype "unspecified"))
      (node (ref "U2") (pin "13") (pinfunction "SYNC#_13") (pintype "unspecified"))
    )
    (net (code "70") (name "SYN3") (class "Default")
      (node (ref "P3") (pin "4") (pinfunction "4_4") (pintype "unspecified"))
      (node (ref "P5") (pin "10") (pinfunction "10_10") (pintype "unspecified"))
      (node (ref "U3") (pin "13") (pinfunction "SYNC#_13") (pintype "unspecified"))
    )
    (net (code "71") (name "SYN4") (class "Default")
      (node (ref "P4") (pin "4") (pinfunction "4_4") (pintype "unspecified"))
      (node (ref "P5") (pin "9") (pinfunction "9_9") (pintype "unspecified"))
      (node (ref "U4") (pin "13") (pinfunction "SYNC#_13") (pintype "unspecified"))
    )
    (net (code "72") (name "VCC") (class "Default")
      (node (ref "P6") (pin "2") (pinfunction "2_2") (pintype "unspecified"))
      (node (ref "R26") (pin "2") (pinfunction "2_2") (pintype "unspecified"))
      (node (ref "SW1") (pin "1") (pinfunction "1_1") (pintype "unspecified"))
      (node (ref "SW2") (pin "1") (pinfunction "1_1") (pintype "unspecified"))
      (node (ref "USBC1") (pin "A4") (pinfunction "VBUS_A4") (pintype "unspecified"))
      (node (ref "USBC1") (pin "A9") (pinfunction "VBUS_A9") (pintype "unspecified"))
      (node (ref "USBC1") (pin "B4") (pinfunction "VBUS_B4") (pintype "unspecified"))
      (node (ref "USBC1") (pin "B9") (pinfunction "VBUS_B9") (pintype "unspecified"))
    )
    (net (code "73") (name "VREG") (class "Default")
      (node (ref "C31") (pin "2") (pinfunction "2_2") (pintype "unspecified"))
      (node (ref "U5") (pin "14") (pinfunction "VREG_14") (pintype "unspecified"))
    )
    (net (code "74") (name "Vref1") (class "Default")
      (node (ref "C42") (pin "2") (pinfunction "2_2") (pintype "unspecified"))
      (node (ref "U1") (pin "4") (pinfunction "VREFIN/VREFOUT_4") (pintype "unspecified"))
      (node (ref "U8") (pin "6") (pinfunction "VOUT_6") (pintype "unspecified"))
    )
    (net (code "75") (name "Vref2") (class "Default")
      (node (ref "C43") (pin "2") (pinfunction "2_2") (pintype "unspecified"))
      (node (ref "U2") (pin "4") (pinfunction "VREFIN/VREFOUT_4") (pintype "unspecified"))
      (node (ref "U9") (pin "6") (pinfunction "VOUT_6") (pintype "unspecified"))
    )
    (net (code "76") (name "Vref3") (class "Default")
      (node (ref "C50") (pin "2") (pinfunction "2_2") (pintype "unspecified"))
      (node (ref "U11") (pin "6") (pinfunction "VOUT_6") (pintype "unspecified"))
      (node (ref "U3") (pin "4") (pinfunction "VREFIN/VREFOUT_4") (pintype "unspecified"))
    )
    (net (code "77") (name "Vref4") (class "Default")
      (node (ref "C51") (pin "2") (pinfunction "2_2") (pintype "unspecified"))
      (node (ref "U12") (pin "6") (pinfunction "VOUT_6") (pintype "unspecified"))
      (node (ref "U4") (pin "4") (pinfunction "VREFIN/VREFOUT_4") (pintype "unspecified"))
    )
    (net (code "78") (name "unconnected-(U1-DNC-Pad9)") (class "Default")
      (node (ref "U1") (pin "9") (pinfunction "DNC_9") (pintype "unspecified+no_connect"))
    )
    (net (code "79") (name "unconnected-(U2-DNC-Pad9)") (class "Default")
      (node (ref "U2") (pin "9") (pinfunction "DNC_9") (pintype "unspecified+no_connect"))
    )
    (net (code "80") (name "unconnected-(U3-DNC-Pad9)") (class "Default")
      (node (ref "U3") (pin "9") (pinfunction "DNC_9") (pintype "unspecified+no_connect"))
    )
    (net (code "81") (name "unconnected-(U4-DNC-Pad9)") (class "Default")
      (node (ref "U4") (pin "9") (pinfunction "DNC_9") (pintype "unspecified+no_connect"))
    )
    (net (code "82") (name "unconnected-(U5-SEQ-Pad3)") (class "Default")
      (node (ref "U5") (pin "3") (pinfunction "SEQ_3") (pintype "unspecified+no_connect"))
    )
    (net (code "83") (name "unconnected-(U5-SLEW-Pad4)") (class "Default")
      (node (ref "U5") (pin "4") (pinfunction "SLEW_4") (pintype "unspecified+no_connect"))
    )
    (net (code "84") (name "unconnected-(U8-NIC-Pad3)") (class "Default")
      (node (ref "U8") (pin "3") (pinfunction "NIC_3") (pintype "unspecified+no_connect"))
    )
    (net (code "85") (name "unconnected-(U8-NIC-Pad7)") (class "Default")
      (node (ref "U8") (pin "7") (pinfunction "NIC_7") (pintype "unspecified+no_connect"))
    )
    (net (code "86") (name "unconnected-(U8-TP-Pad1)") (class "Default")
      (node (ref "U8") (pin "1") (pinfunction "TP_1") (pintype "unspecified+no_connect"))
    )
    (net (code "87") (name "unconnected-(U8-TP-Pad8)") (class "Default")
      (node (ref "U8") (pin "8") (pinfunction "TP_8") (pintype "unspecified+no_connect"))
    )
    (net (code "88") (name "unconnected-(U8-TRIM-Pad5)") (class "Default")
      (node (ref "U8") (pin "5") (pinfunction "TRIM_5") (pintype "unspecified+no_connect"))
    )
    (net (code "89") (name "unconnected-(U9-NIC-Pad3)") (class "Default")
      (node (ref "U9") (pin "3") (pinfunction "NIC_3") (pintype "unspecified+no_connect"))
    )
    (net (code "90") (name "unconnected-(U9-NIC-Pad7)") (class "Default")
      (node (ref "U9") (pin "7") (pinfunction "NIC_7") (pintype "unspecified+no_connect"))
    )
    (net (code "91") (name "unconnected-(U9-TP-Pad1)") (class "Default")
      (node (ref "U9") (pin "1") (pinfunction "TP_1") (pintype "unspecified+no_connect"))
    )
    (net (code "92") (name "unconnected-(U9-TP-Pad8)") (class "Default")
      (node (ref "U9") (pin "8") (pinfunction "TP_8") (pintype "unspecified+no_connect"))
    )
    (net (code "93") (name "unconnected-(U9-TRIM-Pad5)") (class "Default")
      (node (ref "U9") (pin "5") (pinfunction "TRIM_5") (pintype "unspecified+no_connect"))
    )
    (net (code "94") (name "unconnected-(U11-NIC-Pad3)") (class "Default")
      (node (ref "U11") (pin "3") (pinfunction "NIC_3") (pintype "unspecified+no_connect"))
    )
    (net (code "95") (name "unconnected-(U11-NIC-Pad7)") (class "Default")
      (node (ref "U11") (pin "7") (pinfunction "NIC_7") (pintype "unspecified+no_connect"))
    )
    (net (code "96") (name "unconnected-(U11-TP-Pad1)") (class "Default")
      (node (ref "U11") (pin "1") (pinfunction "TP_1") (pintype "unspecified+no_connect"))
    )
    (net (code "97") (name "unconnected-(U11-TP-Pad8)") (class "Default")
      (node (ref "U11") (pin "8") (pinfunction "TP_8") (pintype "unspecified+no_connect"))
    )
    (net (code "98") (name "unconnected-(U11-TRIM-Pad5)") (class "Default")
      (node (ref "U11") (pin "5") (pinfunction "TRIM_5") (pintype "unspecified+no_connect"))
    )
    (net (code "99") (name "unconnected-(U12-NIC-Pad3)") (class "Default")
      (node (ref "U12") (pin "3") (pinfunction "NIC_3") (pintype "unspecified+no_connect"))
    )
    (net (code "100") (name "unconnected-(U12-NIC-Pad7)") (class "Default")
      (node (ref "U12") (pin "7") (pinfunction "NIC_7") (pintype "unspecified+no_connect"))
    )
    (net (code "101") (name "unconnected-(U12-TP-Pad1)") (class "Default")
      (node (ref "U12") (pin "1") (pinfunction "TP_1") (pintype "unspecified+no_connect"))
    )
    (net (code "102") (name "unconnected-(U12-TP-Pad8)") (class "Default")
      (node (ref "U12") (pin "8") (pinfunction "TP_8") (pintype "unspecified+no_connect"))
    )
    (net (code "103") (name "unconnected-(U12-TRIM-Pad5)") (class "Default")
      (node (ref "U12") (pin "5") (pinfunction "TRIM_5") (pintype "unspecified+no_connect"))
    )
    (net (code "104") (name "unconnected-(USBC1-CC1-PadA5)") (class "Default")
      (node (ref "USBC1") (pin "A5") (pinfunction "CC1_A5") (pintype "unspecified+no_connect"))
    )
    (net (code "105") (name "unconnected-(USBC1-CC2-PadB5)") (class "Default")
      (node (ref "USBC1") (pin "B5") (pinfunction "CC2_B5") (pintype "unspecified+no_connect"))
    )
    (net (code "106") (name "unconnected-(USBC1-DN1-PadA7)") (class "Default")
      (node (ref "USBC1") (pin "A7") (pinfunction "DN1_A7") (pintype "unspecified+no_connect"))
    )
    (net (code "107") (name "unconnected-(USBC1-DN2-PadB7)") (class "Default")
      (node (ref "USBC1") (pin "B7") (pinfunction "DN2_B7") (pintype "unspecified+no_connect"))
    )
    (net (code "108") (name "unconnected-(USBC1-DP1-PadA6)") (class "Default")
      (node (ref "USBC1") (pin "A6") (pinfunction "DP1_A6") (pintype "unspecified+no_connect"))
    )
    (net (code "109") (name "unconnected-(USBC1-DP2-PadB6)") (class "Default")
      (node (ref "USBC1") (pin "B6") (pinfunction "DP2_B6") (pintype "unspecified+no_connect"))
    )
    (net (code "110") (name "unconnected-(USBC1-SBU1-PadA8)") (class "Default")
      (node (ref "USBC1") (pin "A8") (pinfunction "SBU1_A8") (pintype "unspecified+no_connect"))
    )
    (net (code "111") (name "unconnected-(USBC1-SBU2-PadB8)") (class "Default")
      (node (ref "USBC1") (pin "B8") (pinfunction "SBU2_B8") (pintype "unspecified+no_connect"))
    )
  )
)
